# sht21_board.net
KiCad netlist of a schematic drawn in EAGLE
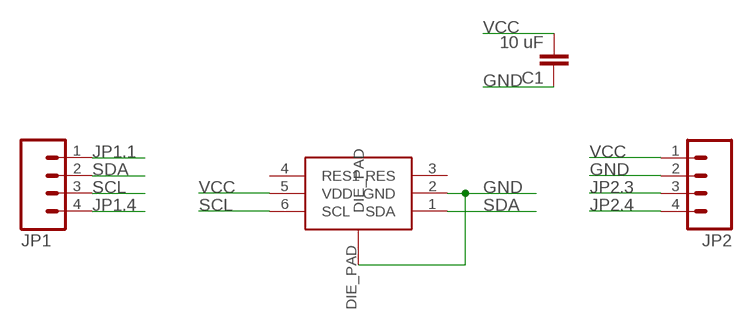
[diagram p0: schematic, sheet 1]

(export (version "E")
  (design (tool "Eeschema 10.0.6"))
  (components
    (comp (ref "C1")
      (value "10 uF")
      (footprint "eagle-import:0805")
      (libsource (lib "eagle-import") (part "CAP0805"))
    )
    (comp (ref "JP1")
      (value "M04PTH")
      (footprint "eagle-import:1X04")
      (libsource (lib "eagle-import") (part "M04PTH"))
    )
    (comp (ref "JP2")
      (value "M04PTH")
      (footprint "eagle-import:1X04")
      (libsource (lib "eagle-import") (part "M04PTH"))
    )
    (comp (ref "U$1")
      (value "SHT21")
      (footprint "eagle-import:SHT21_PADS")
      (libsource (lib "eagle-import") (part "SHT21"))
    )
  )
  (nets
    (net (code "1") (name "/GND") (class "Default")
      (node (ref "C1") (pin "1") (pinfunction "1_1") (pintype "passive"))
      (node (ref "JP2") (pin "2") (pinfunction "2_2") (pintype "passive"))
      (node (ref "U$1") (pin "2") (pinfunction "GND_2") (pintype "bidirectional"))
      (node (ref "U$1") (pin "DIE_PAD") (pinfunction "DIE_PAD_DIE_PAD") (pintype "bidirectional"))
    )
    (net (code "2") (name "/JP1.1") (class "Default")
      (node (ref "JP1") (pin "1") (pinfunction "1_1") (pintype "passive"))
    )
    (net (code "3") (name "/JP1.4") (class "Default")
      (node (ref "JP1") (pin "4") (pinfunction "4_4") (pintype "passive"))
    )
    (net (code "4") (name "/JP2.3") (class "Default")
      (node (ref "JP2") (pin "3") (pinfunction "3_3") (pintype "passive"))
    )
    (net (code "5") (name "/JP2.4") (class "Default")
      (node (ref "JP2") (pin "4") (pinfunction "4_4") (pintype "passive"))
    )
    (net (code "6") (name "/SCL") (class "Default")
      (node (ref "JP1") (pin "3") (pinfunction "3_3") (pintype "passive"))
      (node (ref "U$1") (pin "6") (pinfunction "SCL_6") (pintype "bidirectional"))
    )
    (net (code "7") (name "/SDA") (class "Default")
      (node (ref "JP1") (pin "2") (pinfunction "2_2") (pintype "passive"))
      (node (ref "U$1") (pin "1") (pinfunction "SDA_1") (pintype "bidirectional"))
    )
    (net (code "8") (name "/VCC") (class "Default")
      (node (ref "C1") (pin "2") (pinfunction "2_2") (pintype "passive"))
      (node (ref "JP2") (pin "1") (pinfunction "1_1") (pintype "passive"))
      (node (ref "U$1") (pin "5") (pinfunction "VDD_5") (pintype "bidirectional"))
    )
    (net (code "9") (name "unconnected-(U$1-RES-Pad3)") (class "Default")
      (node (ref "U$1") (pin "3") (pinfunction "RES_3") (pintype "bidirectional"))
    )
    (net (code "10") (name "unconnected-(U$1-RES1-Pad4)") (class "Default")
      (node (ref "U$1") (pin "4") (pinfunction "RES1_4") (pintype "bidirectional"))
    )
  )
)
